# CPU.net
KiCad netlist of a schematic drawn in Altium Designer
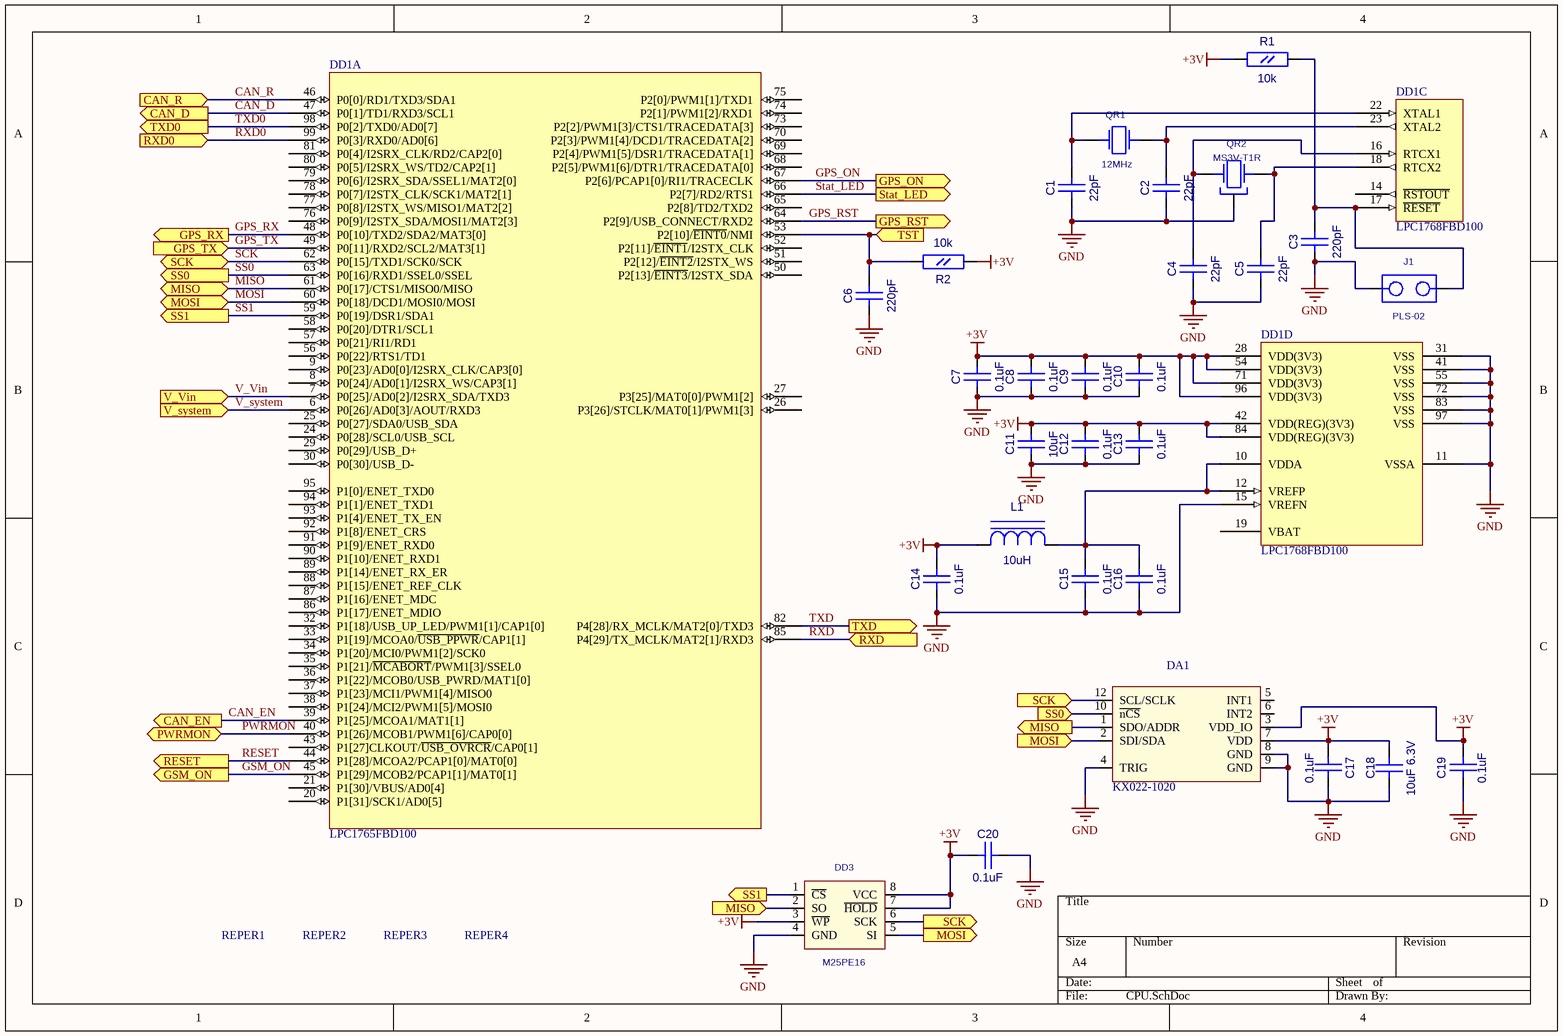
[diagram p0: CPU.SchDoc]

(export (version "E")
  (design (tool "Eeschema 10.0.6"))
  (components
    (comp (ref "C1")
      (value "22pF")
      (footprint "CC0603")
      (description "CC0603")
      (libsource (lib "gprs_modem_2") (part "CC0603"))
    )
    (comp (ref "C2")
      (value "22pF")
      (footprint "CC0603")
      (description "CC0603")
      (libsource (lib "gprs_modem_2") (part "CC0603"))
    )
    (comp (ref "C3")
      (value "220pF")
      (footprint "CC0603")
      (description "CC0603")
      (libsource (lib "gprs_modem_2") (part "CC0603"))
    )
    (comp (ref "C4")
      (value "22pF")
      (footprint "CC0603")
      (description "CC0603")
      (libsource (lib "gprs_modem_2") (part "CC0603"))
    )
    (comp (ref "C5")
      (value "22pF")
      (footprint "CC0603")
      (description "CC0603")
      (libsource (lib "gprs_modem_2") (part "CC0603"))
    )
    (comp (ref "C6")
      (value "220pF")
      (footprint "CC0603")
      (description "CC0603")
      (libsource (lib "gprs_modem_2") (part "CC0603"))
    )
    (comp (ref "C7")
      (value "0.1uF")
      (footprint "CC0603")
      (description "CC0603")
      (libsource (lib "gprs_modem_2") (part "CC0603"))
    )
    (comp (ref "C8")
      (value "0.1uF")
      (footprint "CC0603")
      (description "CC0603")
      (libsource (lib "gprs_modem_2") (part "CC0603"))
    )
    (comp (ref "C9")
      (value "0.1uF")
      (footprint "CC0603")
      (description "CC0603")
      (libsource (lib "gprs_modem_2") (part "CC0603"))
    )
    (comp (ref "C10")
      (value "0.1uF")
      (footprint "CC0603")
      (description "CC0603")
      (libsource (lib "gprs_modem_2") (part "CC0603"))
    )
    (comp (ref "C11")
      (value "10uF")
      (footprint "CC0805")
      (description "CC0805")
      (libsource (lib "gprs_modem_2") (part "CC0805"))
    )
    (comp (ref "C12")
      (value "0.1uF")
      (footprint "CC0603")
      (description "CC0603")
      (libsource (lib "gprs_modem_2") (part "CC0603"))
    )
    (comp (ref "C13")
      (value "0.1uF")
      (footprint "CC0603")
      (description "CC0603")
      (libsource (lib "gprs_modem_2") (part "CC0603"))
    )
    (comp (ref "C14")
      (value "0.1uF")
      (footprint "CC0603")
      (description "CC0603")
      (libsource (lib "gprs_modem_2") (part "CC0603"))
    )
    (comp (ref "C15")
      (value "0.1uF")
      (footprint "CC0603")
      (description "CC0603")
      (libsource (lib "gprs_modem_2") (part "CC0603"))
    )
    (comp (ref "C16")
      (value "0.1uF")
      (footprint "CC0603")
      (description "CC0603")
      (libsource (lib "gprs_modem_2") (part "CC0603"))
    )
    (comp (ref "C17")
      (value "0.1uF")
      (footprint "CC0603")
      (description "CC0603")
      (libsource (lib "gprs_modem_2") (part "CC0603"))
    )
    (comp (ref "C18")
      (value "10uF 6.3V")
      (footprint "CC0805")
      (description "CC0805")
      (libsource (lib "gprs_modem_2") (part "CC0805"))
    )
    (comp (ref "C19")
      (value "0.1uF")
      (footprint "CC0603")
      (description "CC0603")
      (libsource (lib "gprs_modem_2") (part "CC0603"))
    )
    (comp (ref "C20")
      (value "0.1uF")
      (footprint "CC0603")
      (description "CC0603")
      (libsource (lib "gprs_modem_2") (part "CC0603"))
    )
    (comp (ref "DA1")
      (value "KX022-1020")
      (footprint "LGA-12")
      (libsource (lib "gprs_modem_2") (part "KX022-1020"))
    )
    (comp (ref "DD1")
      (value "LPC1765FBD100")
      (footprint "TQFP-100")
      (description "Cortex -M3 32-Bit Microcontroller, 512KB Flash, 64KB RAM, 100-Lead LQFP")
      (libsource (lib "gprs_modem_2") (part "LPC1768FBD100"))
    )
    (comp (ref "DD3")
      (value "M25PE16")
      (footprint "EIAJ_SO8")
      (description "S25FL016A0LMFI01")
      (libsource (lib "gprs_modem_2") (part "S25FL016A0LMFI01"))
    )
    (comp (ref "J1") (value "PLS-02") (footprint "PLS-02") (libsource (lib "gprs_modem_2") (part "PLS-02")))
    (comp (ref "L1")
      (value "10uH")
      (footprint "L0603")
      (description "L0603")
      (libsource (lib "gprs_modem_2") (part "L0603"))
    )
    (comp (ref "QR1")
      (value "12MHz")
      (footprint "AC5032_2")
      (description "AC5032/2")
      (libsource (lib "gprs_modem_2") (part "AC5032_2"))
    )
    (comp (ref "QR2")
      (value "MS3V-T1R")
      (footprint "MS3V-T1R")
      (description "CRYSTAL_32768 Hz")
      (libsource (lib "gprs_modem_2") (part "MS3V-T1R"))
    )
    (comp (ref "R1")
      (value "10k")
      (footprint "RC0603")
      (description "RC0603")
      (libsource (lib "gprs_modem_2") (part "RC0603"))
    )
    (comp (ref "R2")
      (value "10k")
      (footprint "RC0603")
      (description "RC0603")
      (libsource (lib "gprs_modem_2") (part "RC0603"))
    )
    (comp (ref "REPER1")
      (value "REPER1.2")
      (footprint "REPER1.2")
      (libsource (lib "gprs_modem") (part "REPER1.2"))
    )
    (comp (ref "REPER2")
      (value "REPER1.2")
      (footprint "REPER1.2")
      (libsource (lib "gprs_modem") (part "REPER1.2"))
    )
    (comp (ref "REPER3")
      (value "REPER1.2")
      (footprint "REPER1.2")
      (libsource (lib "gprs_modem") (part "REPER1.2"))
    )
    (comp (ref "REPER4")
      (value "REPER1.2")
      (footprint "REPER1.2")
      (libsource (lib "gprs_modem") (part "REPER1.2"))
    )
  )
  (nets
    (net (code "1") (name "+3V") (class "Default")
      (node (ref "C10") (pin "2") (pinfunction "B_2") (pintype "passive"))
      (node (ref "C11") (pin "2") (pinfunction "B_2") (pintype "passive"))
      (node (ref "C12") (pin "2") (pinfunction "B_2") (pintype "passive"))
      (node (ref "C13") (pin "2") (pinfunction "B_2") (pintype "passive"))
      (node (ref "C14") (pin "2") (pinfunction "B_2") (pintype "passive"))
      (node (ref "C17") (pin "1") (pinfunction "A_1") (pintype "passive"))
      (node (ref "C18") (pin "2") (pinfunction "B_2") (pintype "passive"))
      (node (ref "C19") (pin "1") (pinfunction "A_1") (pintype "passive"))
      (node (ref "C20") (pin "1") (pinfunction "A_1") (pintype "passive"))
      (node (ref "C7") (pin "2") (pinfunction "B_2") (pintype "passive"))
      (node (ref "C8") (pin "2") (pinfunction "B_2") (pintype "passive"))
      (node (ref "C9") (pin "2") (pinfunction "B_2") (pintype "passive"))
      (node (ref "DA1") (pin "3") (pinfunction "VDD_IO_3") (pintype "passive"))
      (node (ref "DA1") (pin "7") (pinfunction "VDD_7") (pintype "passive"))
      (node (ref "DD1") (pin "28") (pinfunction "VDD(3V3)_28") (pintype "power_in"))
      (node (ref "DD1") (pin "42") (pinfunction "VDD(REG)(3V3)_42") (pintype "power_in"))
      (node (ref "DD1") (pin "54") (pinfunction "VDD(3V3)_54") (pintype "power_in"))
      (node (ref "DD1") (pin "71") (pinfunction "VDD(3V3)_71") (pintype "power_in"))
      (node (ref "DD1") (pin "84") (pinfunction "VDD(REG)(3V3)_84") (pintype "power_in"))
      (node (ref "DD1") (pin "96") (pinfunction "VDD(3V3)_96") (pintype "power_in"))
      (node (ref "DD3") (pin "3") (pinfunction "~{WP}_3") (pintype "passive"))
      (node (ref "DD3") (pin "7") (pinfunction "~{HOLD}_7") (pintype "passive"))
      (node (ref "DD3") (pin "8") (pinfunction "VCC_8") (pintype "passive"))
      (node (ref "L1") (pin "1") (pinfunction "A_1") (pintype "passive"))
      (node (ref "R1") (pin "1") (pinfunction "A_1") (pintype "passive"))
      (node (ref "R2") (pin "1") (pinfunction "A_1") (pintype "passive"))
    )
    (net (code "2") (name "/CAN_D") (class "Default")
      (node (ref "DD1") (pin "47") (pinfunction "P0[1]/TD1/RXD3/SCL1_47") (pintype "bidirectional"))
    )
    (net (code "3") (name "/CAN_EN") (class "Default")
      (node (ref "DD1") (pin "39") (pinfunction "P1[25]/MCOA1/MAT1[1]_39") (pintype "bidirectional"))
    )
    (net (code "4") (name "/CAN_R") (class "Default")
      (node (ref "DD1") (pin "46") (pinfunction "P0[0]/RD1/TXD3/SDA1_46") (pintype "bidirectional"))
    )
    (net (code "5") (name "/GPS_ON") (class "Default")
      (node (ref "DD1") (pin "67") (pinfunction "P2[6]/PCAP1[0]/RI1/TRACECLK_67") (pintype "bidirectional"))
    )
    (net (code "6") (name "/GPS_RST") (class "Default")
      (node (ref "DD1") (pin "64") (pinfunction "P2[9]/USB_CONNECT/RXD2_64") (pintype "bidirectional"))
    )
    (net (code "7") (name "/GPS_RX") (class "Default")
      (node (ref "DD1") (pin "48") (pinfunction "P0[10]/TXD2/SDA2/MAT3[0]_48") (pintype "bidirectional"))
    )
    (net (code "8") (name "/GPS_TX") (class "Default")
      (node (ref "DD1") (pin "49") (pinfunction "P0[11]/RXD2/SCL2/MAT3[1]_49") (pintype "bidirectional"))
    )
    (net (code "9") (name "/GSM_ON") (class "Default")
      (node (ref "DD1") (pin "45") (pinfunction "P1[29]/MCOB2/PCAP1[1]/MAT0[1]_45") (pintype "bidirectional"))
    )
    (net (code "10") (name "/MISO") (class "Default")
      (node (ref "DA1") (pin "1") (pinfunction "SDO/ADDR_1") (pintype "passive"))
      (node (ref "DD1") (pin "61") (pinfunction "P0[17]/CTS1/MISO0/MISO_61") (pintype "bidirectional"))
      (node (ref "DD3") (pin "2") (pinfunction "SO_2") (pintype "passive"))
    )
    (net (code "11") (name "/MOSI") (class "Default")
      (node (ref "DA1") (pin "2") (pinfunction "SDI/SDA_2") (pintype "passive"))
      (node (ref "DD1") (pin "60") (pinfunction "P0[18]/DCD1/MOSI0/MOSI_60") (pintype "bidirectional"))
      (node (ref "DD3") (pin "5") (pinfunction "SI_5") (pintype "passive"))
    )
    (net (code "12") (name "/PWRMON") (class "Default")
      (node (ref "DD1") (pin "40") (pinfunction "P1[26]/MCOB1/PWM1[6]/CAP0[0]_40") (pintype "bidirectional"))
    )
    (net (code "13") (name "/RESET") (class "Default")
      (node (ref "DD1") (pin "44") (pinfunction "P1[28]/MCOA2/PCAP1[0]/MAT0[0]_44") (pintype "bidirectional"))
    )
    (net (code "14") (name "/RXD") (class "Default")
      (node (ref "DD1") (pin "85") (pinfunction "P4[29]/TX_MCLK/MAT2[1]/RXD3_85") (pintype "bidirectional"))
    )
    (net (code "15") (name "/RXD0") (class "Default")
      (node (ref "DD1") (pin "99") (pinfunction "P0[3]/RXD0/AD0[6]_99") (pintype "bidirectional"))
    )
    (net (code "16") (name "/SCK") (class "Default")
      (node (ref "DA1") (pin "12") (pinfunction "SCL/SCLK_12") (pintype "passive"))
      (node (ref "DD1") (pin "62") (pinfunction "P0[15]/TXD1/SCK0/SCK_62") (pintype "bidirectional"))
      (node (ref "DD3") (pin "6") (pinfunction "SCK_6") (pintype "passive"))
    )
    (net (code "17") (name "/SS0") (class "Default")
      (node (ref "DA1") (pin "10") (pinfunction "~{nCS}_10") (pintype "passive"))
      (node (ref "DD1") (pin "63") (pinfunction "P0[16]/RXD1/SSEL0/SSEL_63") (pintype "bidirectional"))
    )
    (net (code "18") (name "/SS1") (class "Default")
      (node (ref "DD1") (pin "59") (pinfunction "P0[19]/DSR1/SDA1_59") (pintype "bidirectional"))
      (node (ref "DD3") (pin "1") (pinfunction "~{CS}_1") (pintype "passive"))
    )
    (net (code "19") (name "/Stat_LED") (class "Default")
      (node (ref "DD1") (pin "66") (pinfunction "P2[7]/RD2/RTS1_66") (pintype "bidirectional"))
    )
    (net (code "20") (name "/TST") (class "Default")
      (node (ref "C6") (pin "2") (pinfunction "B_2") (pintype "passive"))
      (node (ref "DD1") (pin "53") (pinfunction "P2[10]/~{EINT0}/NMI_53") (pintype "bidirectional"))
      (node (ref "R2") (pin "2") (pinfunction "B_2") (pintype "passive"))
    )
    (net (code "21") (name "/TXD") (class "Default")
      (node (ref "DD1") (pin "82") (pinfunction "P4[28]/RX_MCLK/MAT2[0]/TXD3_82") (pintype "bidirectional"))
    )
    (net (code "22") (name "/TXD0") (class "Default")
      (node (ref "DD1") (pin "98") (pinfunction "P0[2]/TXD0/AD0[7]_98") (pintype "bidirectional"))
    )
    (net (code "23") (name "/V_Vin") (class "Default")
      (node (ref "DD1") (pin "7") (pinfunction "P0[25]/AD0[2]/I2SRX_SDA/TXD3_7") (pintype "bidirectional"))
    )
    (net (code "24") (name "/V_system") (class "Default")
      (node (ref "DD1") (pin "6") (pinfunction "P0[26]/AD0[3]/AOUT/RXD3_6") (pintype "bidirectional"))
    )
    (net (code "25") (name "GND") (class "Default")
      (node (ref "C1") (pin "1") (pinfunction "A_1") (pintype "passive"))
      (node (ref "C10") (pin "1") (pinfunction "A_1") (pintype "passive"))
      (node (ref "C11") (pin "1") (pinfunction "A_1") (pintype "passive"))
      (node (ref "C12") (pin "1") (pinfunction "A_1") (pintype "passive"))
      (node (ref "C13") (pin "1") (pinfunction "A_1") (pintype "passive"))
      (node (ref "C14") (pin "1") (pinfunction "A_1") (pintype "passive"))
      (node (ref "C15") (pin "1") (pinfunction "A_1") (pintype "passive"))
      (node (ref "C16") (pin "1") (pinfunction "A_1") (pintype "passive"))
      (node (ref "C17") (pin "2") (pinfunction "B_2") (pintype "passive"))
      (node (ref "C18") (pin "1") (pinfunction "A_1") (pintype "passive"))
      (node (ref "C19") (pin "2") (pinfunction "B_2") (pintype "passive"))
      (node (ref "C2") (pin "1") (pinfunction "A_1") (pintype "passive"))
      (node (ref "C20") (pin "2") (pinfunction "B_2") (pintype "passive"))
      (node (ref "C3") (pin "1") (pinfunction "A_1") (pintype "passive"))
      (node (ref "C4") (pin "1") (pinfunction "A_1") (pintype "passive"))
      (node (ref "C5") (pin "1") (pinfunction "A_1") (pintype "passive"))
      (node (ref "C6") (pin "1") (pinfunction "A_1") (pintype "passive"))
      (node (ref "C7") (pin "1") (pinfunction "A_1") (pintype "passive"))
      (node (ref "C8") (pin "1") (pinfunction "A_1") (pintype "passive"))
      (node (ref "C9") (pin "1") (pinfunction "A_1") (pintype "passive"))
      (node (ref "DA1") (pin "4") (pinfunction "TRIG_4") (pintype "passive"))
      (node (ref "DA1") (pin "8") (pinfunction "GND_8") (pintype "passive"))
      (node (ref "DA1") (pin "9") (pinfunction "GND_9") (pintype "passive"))
      (node (ref "DD1") (pin "11") (pinfunction "VSSA_11") (pintype "power_in"))
      (node (ref "DD1") (pin "15") (pinfunction "VREFN_15") (pintype "input"))
      (node (ref "DD1") (pin "31") (pinfunction "VSS_31") (pintype "power_in"))
      (node (ref "DD1") (pin "41") (pinfunction "VSS_41") (pintype "power_in"))
      (node (ref "DD1") (pin "55") (pinfunction "VSS_55") (pintype "power_in"))
      (node (ref "DD1") (pin "72") (pinfunction "VSS_72") (pintype "power_in"))
      (node (ref "DD1") (pin "83") (pinfunction "VSS_83") (pintype "power_in"))
      (node (ref "DD1") (pin "97") (pinfunction "VSS_97") (pintype "power_in"))
      (node (ref "DD3") (pin "4") (pinfunction "GND_4") (pintype "passive"))
      (node (ref "J1") (pin "1") (pintype "passive"))
      (node (ref "QR2") (pin "3") (pinfunction "3_3") (pintype "passive"))
    )
    (net (code "26") (name "Net-(C1-B)") (class "Default")
      (node (ref "C1") (pin "2") (pinfunction "B_2") (pintype "passive"))
      (node (ref "DD1") (pin "22") (pinfunction "XTAL1_22") (pintype "input"))
      (node (ref "QR1") (pin "1") (pintype "passive"))
    )
    (net (code "27") (name "Net-(C2-B)") (class "Default")
      (node (ref "C2") (pin "2") (pinfunction "B_2") (pintype "passive"))
      (node (ref "DD1") (pin "23") (pinfunction "XTAL2_23") (pintype "output"))
      (node (ref "QR1") (pin "2") (pintype "passive"))
    )
    (net (code "28") (name "Net-(C3-B)") (class "Default")
      (node (ref "C3") (pin "2") (pinfunction "B_2") (pintype "passive"))
      (node (ref "DD1") (pin "17") (pinfunction "~{RESET}_17") (pintype "input"))
      (node (ref "J1") (pin "2") (pintype "passive"))
      (node (ref "R1") (pin "2") (pinfunction "B_2") (pintype "passive"))
    )
    (net (code "29") (name "Net-(C4-B)") (class "Default")
      (node (ref "C4") (pin "2") (pinfunction "B_2") (pintype "passive"))
      (node (ref "DD1") (pin "16") (pinfunction "RTCX1_16") (pintype "input"))
      (node (ref "QR2") (pin "1") (pinfunction "X1_1") (pintype "passive"))
    )
    (net (code "30") (name "Net-(C5-B)") (class "Default")
      (node (ref "C5") (pin "2") (pinfunction "B_2") (pintype "passive"))
      (node (ref "DD1") (pin "18") (pinfunction "RTCX2_18") (pintype "output"))
      (node (ref "QR2") (pin "2") (pinfunction "X2_2") (pintype "passive"))
    )
    (net (code "31") (name "Net-(C15-B)") (class "Default")
      (node (ref "C15") (pin "2") (pinfunction "B_2") (pintype "passive"))
      (node (ref "C16") (pin "2") (pinfunction "B_2") (pintype "passive"))
      (node (ref "DD1") (pin "10") (pinfunction "VDDA_10") (pintype "power_in"))
      (node (ref "DD1") (pin "12") (pinfunction "VREFP_12") (pintype "input"))
      (node (ref "L1") (pin "2") (pinfunction "C_2") (pintype "passive"))
    )
    (net (code "32") (name "unconnected-(DA1-INT1-Pad5)") (class "Default")
      (node (ref "DA1") (pin "5") (pinfunction "INT1_5") (pintype "passive"))
    )
    (net (code "33") (name "unconnected-(DA1-INT2-Pad6)") (class "Default")
      (node (ref "DA1") (pin "6") (pinfunction "INT2_6") (pintype "passive"))
    )
    (net (code "34") (name "unconnected-(DD1A-P0[4]{slash}I2SRX_CLK{slash}RD2{slash}CAP2[0]-Pad81)") (class "Default")
      (node (ref "DD1") (pin "81") (pinfunction "P0[4]/I2SRX_CLK/RD2/CAP2[0]_81") (pintype "bidirectional"))
    )
    (net (code "35") (name "unconnected-(DD1A-P0[5]{slash}I2SRX_WS{slash}TD2{slash}CAP2[1]-Pad80)") (class "Default")
      (node (ref "DD1") (pin "80") (pinfunction "P0[5]/I2SRX_WS/TD2/CAP2[1]_80") (pintype "bidirectional"))
    )
    (net (code "36") (name "unconnected-(DD1A-P0[6]{slash}I2SRX_SDA{slash}SSEL1{slash}MAT2[0]-Pad79)") (class "Default")
      (node (ref "DD1") (pin "79") (pinfunction "P0[6]/I2SRX_SDA/SSEL1/MAT2[0]_79") (pintype "bidirectional"))
    )
    (net (code "37") (name "unconnected-(DD1A-P0[7]{slash}I2STX_CLK{slash}SCK1{slash}MAT2[1]-Pad78)") (class "Default")
      (node (ref "DD1") (pin "78") (pinfunction "P0[7]/I2STX_CLK/SCK1/MAT2[1]_78") (pintype "bidirectional"))
    )
    (net (code "38") (name "unconnected-(DD1A-P0[8]{slash}I2STX_WS{slash}MISO1{slash}MAT2[2]-Pad77)") (class "Default")
      (node (ref "DD1") (pin "77") (pinfunction "P0[8]/I2STX_WS/MISO1/MAT2[2]_77") (pintype "bidirectional"))
    )
    (net (code "39") (name "unconnected-(DD1A-P0[9]{slash}I2STX_SDA{slash}MOSI1{slash}MAT2[3]-Pad76)") (class "Default")
      (node (ref "DD1") (pin "76") (pinfunction "P0[9]/I2STX_SDA/MOSI1/MAT2[3]_76") (pintype "bidirectional"))
    )
    (net (code "40") (name "unconnected-(DD1A-P0[20]{slash}DTR1{slash}SCL1-Pad58)") (class "Default")
      (node (ref "DD1") (pin "58") (pinfunction "P0[20]/DTR1/SCL1_58") (pintype "bidirectional"))
    )
    (net (code "41") (name "unconnected-(DD1A-P0[21]{slash}RI1{slash}RD1-Pad57)") (class "Default")
      (node (ref "DD1") (pin "57") (pinfunction "P0[21]/RI1/RD1_57") (pintype "bidirectional"))
    )
    (net (code "42") (name "unconnected-(DD1A-P0[22]{slash}RTS1{slash}TD1-Pad56)") (class "Default")
      (node (ref "DD1") (pin "56") (pinfunction "P0[22]/RTS1/TD1_56") (pintype "bidirectional"))
    )
    (net (code "43") (name "unconnected-(DD1A-P0[23]{slash}AD0[0]{slash}I2SRX_CLK{slash}CAP3[0]-Pad9)") (class "Default")
      (node (ref "DD1") (pin "9") (pinfunction "P0[23]/AD0[0]/I2SRX_CLK/CAP3[0]_9") (pintype "bidirectional"))
    )
    (net (code "44") (name "unconnected-(DD1A-P0[24]{slash}AD0[1]{slash}I2SRX_WS{slash}CAP3[1]-Pad8)") (class "Default")
      (node (ref "DD1") (pin "8") (pinfunction "P0[24]/AD0[1]/I2SRX_WS/CAP3[1]_8") (pintype "bidirectional"))
    )
    (net (code "45") (name "unconnected-(DD1A-P0[27]{slash}SDA0{slash}USB_SDA-Pad25)") (class "Default")
      (node (ref "DD1") (pin "25") (pinfunction "P0[27]/SDA0/USB_SDA_25") (pintype "bidirectional"))
    )
    (net (code "46") (name "unconnected-(DD1A-P0[28]{slash}SCL0{slash}USB_SCL-Pad24)") (class "Default")
      (node (ref "DD1") (pin "24") (pinfunction "P0[28]/SCL0/USB_SCL_24") (pintype "bidirectional"))
    )
    (net (code "47") (name "unconnected-(DD1A-P0[29]{slash}USB_D+-Pad29)") (class "Default")
      (node (ref "DD1") (pin "29") (pinfunction "P0[29]/USB_D+_29") (pintype "bidirectional"))
    )
    (net (code "48") (name "unconnected-(DD1A-P0[30]{slash}USB_D--Pad30)") (class "Default")
      (node (ref "DD1") (pin "30") (pinfunction "P0[30]/USB_D-_30") (pintype "bidirectional"))
    )
    (net (code "49") (name "unconnected-(DD1A-P1[0]{slash}ENET_TXD0-Pad95)") (class "Default")
      (node (ref "DD1") (pin "95") (pinfunction "P1[0]/ENET_TXD0_95") (pintype "bidirectional"))
    )
    (net (code "50") (name "unconnected-(DD1A-P1[1]{slash}ENET_TXD1-Pad94)") (class "Default")
      (node (ref "DD1") (pin "94") (pinfunction "P1[1]/ENET_TXD1_94") (pintype "bidirectional"))
    )
    (net (code "51") (name "unconnected-(DD1A-P1[4]{slash}ENET_TX_EN-Pad93)") (class "Default")
      (node (ref "DD1") (pin "93") (pinfunction "P1[4]/ENET_TX_EN_93") (pintype "bidirectional"))
    )
    (net (code "52") (name "unconnected-(DD1A-P1[8]{slash}ENET_CRS-Pad92)") (class "Default")
      (node (ref "DD1") (pin "92") (pinfunction "P1[8]/ENET_CRS_92") (pintype "bidirectional"))
    )
    (net (code "53") (name "unconnected-(DD1A-P1[9]{slash}ENET_RXD0-Pad91)") (class "Default")
      (node (ref "DD1") (pin "91") (pinfunction "P1[9]/ENET_RXD0_91") (pintype "bidirectional"))
    )
    (net (code "54") (name "unconnected-(DD1A-P1[10]{slash}ENET_RXD1-Pad90)") (class "Default")
      (node (ref "DD1") (pin "90") (pinfunction "P1[10]/ENET_RXD1_90") (pintype "bidirectional"))
    )
    (net (code "55") (name "unconnected-(DD1A-P1[14]{slash}ENET_RX_ER-Pad89)") (class "Default")
      (node (ref "DD1") (pin "89") (pinfunction "P1[14]/ENET_RX_ER_89") (pintype "bidirectional"))
    )
    (net (code "56") (name "unconnected-(DD1A-P1[15]{slash}ENET_REF_CLK-Pad88)") (class "Default")
      (node (ref "DD1") (pin "88") (pinfunction "P1[15]/ENET_REF_CLK_88") (pintype "bidirectional"))
    )
    (net (code "57") (name "unconnected-(DD1A-P1[16]{slash}ENET_MDC-Pad87)") (class "Default")
      (node (ref "DD1") (pin "87") (pinfunction "P1[16]/ENET_MDC_87") (pintype "bidirectional"))
    )
    (net (code "58") (name "unconnected-(DD1A-P1[17]{slash}ENET_MDIO-Pad86)") (class "Default")
      (node (ref "DD1") (pin "86") (pinfunction "P1[17]/ENET_MDIO_86") (pintype "bidirectional"))
    )
    (net (code "59") (name "unconnected-(DD1A-P1[18]{slash}USB_UP_LED{slash}PWM1[1]{slash}CAP1[0]-Pad32)") (class "Default")
      (node (ref "DD1") (pin "32") (pinfunction "P1[18]/USB_UP_LED/PWM1[1]/CAP1[0]_32") (pintype "bidirectional"))
    )
    (net (code "60") (name "unconnected-(DD1A-P1[19]{slash}MCOA0{slash}~{USB_PPWR}{slash}CAP1[1]-Pad33)") (class "Default")
      (node (ref "DD1") (pin "33") (pinfunction "P1[19]/MCOA0/~{USB_PPWR}/CAP1[1]_33") (pintype "bidirectional"))
    )
    (net (code "61") (name "unconnected-(DD1A-P1[20]{slash}MCI0{slash}PWM1[2]{slash}SCK0-Pad34)") (class "Default")
      (node (ref "DD1") (pin "34") (pinfunction "P1[20]/MCI0/PWM1[2]/SCK0_34") (pintype "bidirectional"))
    )
    (net (code "62") (name "unconnected-(DD1A-P1[21]{slash}~{MCABORT}{slash}PWM1[3]{slash}SSEL0-Pad35)") (class "Default")
      (node (ref "DD1") (pin "35") (pinfunction "P1[21]/~{MCABORT}/PWM1[3]/SSEL0_35") (pintype "bidirectional"))
    )
    (net (code "63") (name "unconnected-(DD1A-P1[22]{slash}MCOB0{slash}USB_PWRD{slash}MAT1[0]-Pad36)") (class "Default")
      (node (ref "DD1") (pin "36") (pinfunction "P1[22]/MCOB0/USB_PWRD/MAT1[0]_36") (pintype "bidirectional"))
    )
    (net (code "64") (name "unconnected-(DD1A-P1[23]{slash}MCI1{slash}PWM1[4]{slash}MISO0-Pad37)") (class "Default")
      (node (ref "DD1") (pin "37") (pinfunction "P1[23]/MCI1/PWM1[4]/MISO0_37") (pintype "bidirectional"))
    )
    (net (code "65") (name "unconnected-(DD1A-P1[24]{slash}MCI2{slash}PWM1[5]{slash}MOSI0-Pad38)") (class "Default")
      (node (ref "DD1") (pin "38") (pinfunction "P1[24]/MCI2/PWM1[5]/MOSI0_38") (pintype "bidirectional"))
    )
    (net (code "66") (name "unconnected-(DD1A-P1[27]CLKOUT{slash}~{USB_OVRCR}{slash}CAP0[1]-Pad43)") (class "Default")
      (node (ref "DD1") (pin "43") (pinfunction "P1[27]CLKOUT/~{USB_OVRCR}/CAP0[1]_43") (pintype "bidirectional"))
    )
    (net (code "67") (name "unconnected-(DD1A-P1[30]{slash}VBUS{slash}AD0[4]-Pad21)") (class "Default")
      (node (ref "DD1") (pin "21") (pinfunction "P1[30]/VBUS/AD0[4]_21") (pintype "bidirectional"))
    )
    (net (code "68") (name "unconnected-(DD1A-P1[31]{slash}SCK1{slash}AD0[5]-Pad20)") (class "Default")
      (node (ref "DD1") (pin "20") (pinfunction "P1[31]/SCK1/AD0[5]_20") (pintype "bidirectional"))
    )
    (net (code "69") (name "unconnected-(DD1A-P2[0]{slash}PWM1[1]{slash}TXD1-Pad75)") (class "Default")
      (node (ref "DD1") (pin "75") (pinfunction "P2[0]/PWM1[1]/TXD1_75") (pintype "bidirectional"))
    )
    (net (code "70") (name "unconnected-(DD1A-P2[1]{slash}PWM1[2]{slash}RXD1-Pad74)") (class "Default")
      (node (ref "DD1") (pin "74") (pinfunction "P2[1]/PWM1[2]/RXD1_74") (pintype "bidirectional"))
    )
    (net (code "71") (name "unconnected-(DD1A-P2[2]{slash}PWM1[3]{slash}CTS1{slash}TRACEDATA[3]-Pad73)") (class "Default")
      (node (ref "DD1") (pin "73") (pinfunction "P2[2]/PWM1[3]/CTS1/TRACEDATA[3]_73") (pintype "bidirectional"))
    )
    (net (code "72") (name "unconnected-(DD1A-P2[3]{slash}PWM1[4]{slash}DCD1{slash}TRACEDATA[2]-Pad70)") (class "Default")
      (node (ref "DD1") (pin "70") (pinfunction "P2[3]/PWM1[4]/DCD1/TRACEDATA[2]_70") (pintype "bidirectional"))
    )
    (net (code "73") (name "unconnected-(DD1A-P2[4]{slash}PWM1[5]{slash}DSR1{slash}TRACEDATA[1]-Pad69)") (class "Default")
      (node (ref "DD1") (pin "69") (pinfunction "P2[4]/PWM1[5]/DSR1/TRACEDATA[1]_69") (pintype "bidirectional"))
    )
    (net (code "74") (name "unconnected-(DD1A-P2[5]{slash}PWM1[6]{slash}DTR1{slash}TRACEDATA[0]-Pad68)") (class "Default")
      (node (ref "DD1") (pin "68") (pinfunction "P2[5]/PWM1[6]/DTR1/TRACEDATA[0]_68") (pintype "bidirectional"))
    )
    (net (code "75") (name "unconnected-(DD1A-P2[8]{slash}TD2{slash}TXD2-Pad65)") (class "Default")
      (node (ref "DD1") (pin "65") (pinfunction "P2[8]/TD2/TXD2_65") (pintype "bidirectional"))
    )
    (net (code "76") (name "unconnected-(DD1A-P2[11]{slash}~{EINT1}{slash}I2STX_CLK-Pad52)") (class "Default")
      (node (ref "DD1") (pin "52") (pinfunction "P2[11]/~{EINT1}/I2STX_CLK_52") (pintype "bidirectional"))
    )
    (net (code "77") (name "unconnected-(DD1A-P2[12]{slash}~{EINT2}{slash}I2STX_WS-Pad51)") (class "Default")
      (node (ref "DD1") (pin "51") (pinfunction "P2[12]/~{EINT2}/I2STX_WS_51") (pintype "bidirectional"))
    )
    (net (code "78") (name "unconnected-(DD1A-P2[13]{slash}~{EINT3}{slash}I2STX_SDA-Pad50)") (class "Default")
      (node (ref "DD1") (pin "50") (pinfunction "P2[13]/~{EINT3}/I2STX_SDA_50") (pintype "bidirectional"))
    )
    (net (code "79") (name "unconnected-(DD1A-P3[25]{slash}MAT0[0]{slash}PWM1[2]-Pad27)") (class "Default")
      (node (ref "DD1") (pin "27") (pinfunction "P3[25]/MAT0[0]/PWM1[2]_27") (pintype "bidirectional"))
    )
    (net (code "80") (name "unconnected-(DD1A-P3[26]{slash}STCLK{slash}MAT0[1]{slash}PWM1[3]-Pad26)") (class "Default")
      (node (ref "DD1") (pin "26") (pinfunction "P3[26]/STCLK/MAT0[1]/PWM1[3]_26") (pintype "bidirectional"))
    )
    (net (code "81") (name "unconnected-(DD1C-~{RSTOUT}-Pad14)") (class "Default")
      (node (ref "DD1") (pin "14") (pinfunction "~{RSTOUT}_14") (pintype "output"))
    )
    (net (code "82") (name "unconnected-(DD1D-VBAT-Pad19)") (class "Default")
      (node (ref "DD1") (pin "19") (pinfunction "VBAT_19") (pintype "power_in"))
    )
    (net (code "83") (name "unconnected-(REPER1-Pad1)") (class "Default")
      (node (ref "REPER1") (pin "1") (pintype "passive"))
    )
    (net (code "84") (name "unconnected-(REPER2-Pad1)") (class "Default")
      (node (ref "REPER2") (pin "1") (pintype "passive"))
    )
    (net (code "85") (name "unconnected-(REPER3-Pad1)") (class "Default")
      (node (ref "REPER3") (pin "1") (pintype "passive"))
    )
    (net (code "86") (name "unconnected-(REPER4-Pad1)") (class "Default")
      (node (ref "REPER4") (pin "1") (pintype "passive"))
    )
  )
)
